# Sheet2.net
KiCad netlist of a schematic drawn in Altium Designer
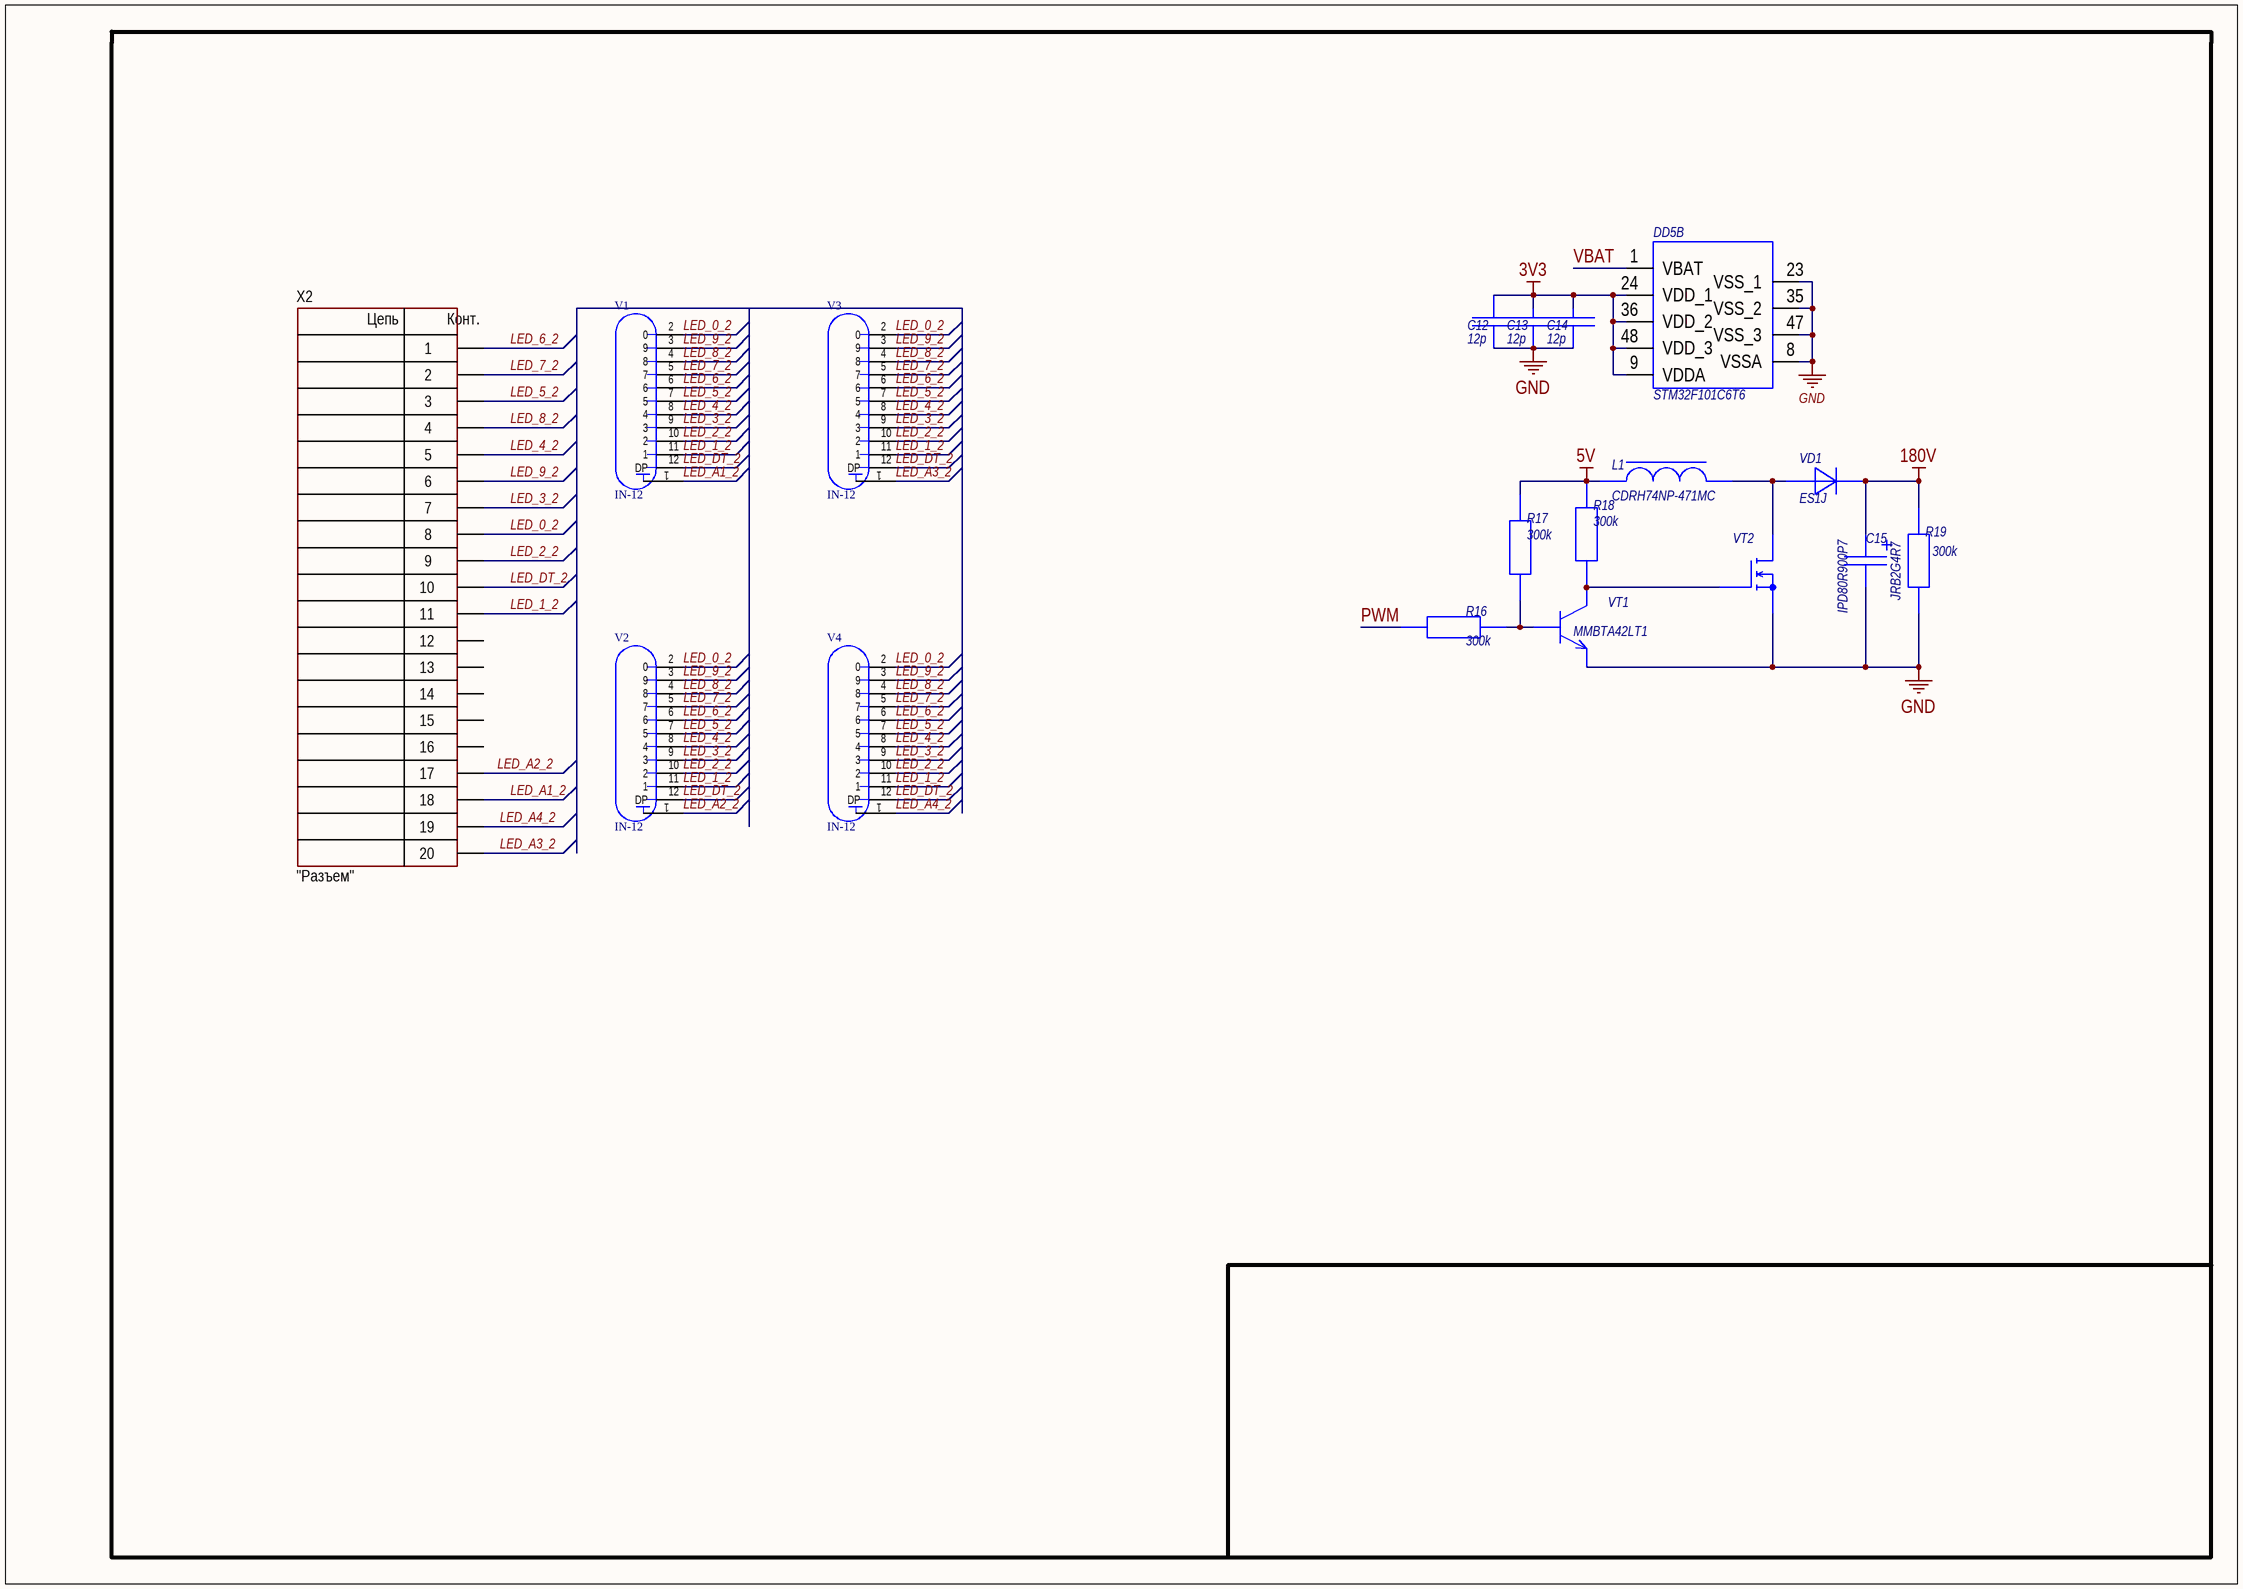
[diagram p0: Sheet2.SchDoc]

(export (version "E")
  (design (tool "Eeschema 10.0.6"))
  (components
    (comp (ref "C12")
      (value "12p")
      (footprint "GRIx4:CAPACITOR 0603")
      (description "Capacitor")
      (libsource (lib "GRIx4_1") (part "SMD-CAP"))
    )
    (comp (ref "C13")
      (value "12p")
      (footprint "GRIx4:CAPACITOR 0603")
      (description "Capacitor")
      (libsource (lib "GRIx4_1") (part "SMD-CAP"))
    )
    (comp (ref "C14")
      (value "12p")
      (footprint "GRIx4:CAPACITOR 0603")
      (description "Capacitor")
      (libsource (lib "GRIx4_1") (part "SMD-CAP"))
    )
    (comp (ref "C15")
      (value "JRB2G4R7")
      (footprint "CAPASITOR R10")
      (description "TC-D")
      (libsource (lib "GRIx4_1") (part "TC-D"))
    )
    (comp (ref "DD5")
      (value "STM32F101C6T6")
      (footprint "48-LQFP")
      (description "Controller")
      (libsource (lib "GRIx4_1") (part "STM32F103C8T6"))
    )
    (comp (ref "L1")
      (value "CDRH74NP-471MC")
      (footprint "SRR0603B")
      (libsource (lib "GRIx4_1") (part "Inductor"))
    )
    (comp (ref "R16")
      (value "300k")
      (footprint "RESISTOR 0603")
      (description "Resistor")
      (libsource (lib "GRIx4_1") (part "SMD-RES_1"))
    )
    (comp (ref "R17")
      (value "300k")
      (footprint "RESISTOR 0603")
      (description "Resistor")
      (libsource (lib "GRIx4_1") (part "SMD-RES_1"))
    )
    (comp (ref "R18")
      (value "300k")
      (footprint "RESISTOR 0603")
      (description "Resistor")
      (libsource (lib "GRIx4_1") (part "SMD-RES_1"))
    )
    (comp (ref "R19")
      (value "300k")
      (footprint "RESISTOR 0805")
      (description "Resistor")
      (libsource (lib "GRIx4_1") (part "SMD-RES_1"))
    )
    (comp (ref "V1")
      (value "IN-12")
      (footprint "GRIx4:DIODE: IN-12")
      (description "Vacuum Indicator")
      (fields (field (name "PUBLISHER") "Altium Limited"))
      (libsource (lib "GRIx4_1") (part "IN-12"))
    )
    (comp (ref "V2")
      (value "IN-12")
      (footprint "GRIx4:DIODE: IN-12")
      (description "Vacuum Indicator")
      (fields (field (name "PUBLISHER") "Altium Limited"))
      (libsource (lib "GRIx4_1") (part "IN-12"))
    )
    (comp (ref "V3")
      (value "IN-12")
      (footprint "GRIx4:DIODE: IN-12")
      (description "Vacuum Indicator")
      (fields (field (name "PUBLISHER") "Altium Limited"))
      (libsource (lib "GRIx4_1") (part "IN-12"))
    )
    (comp (ref "V4")
      (value "IN-12")
      (footprint "GRIx4:DIODE: IN-12")
      (description "Vacuum Indicator")
      (fields (field (name "PUBLISHER") "Altium Limited"))
      (libsource (lib "GRIx4_1") (part "IN-12"))
    )
    (comp (ref "VD1")
      (value "ES1J")
      (footprint "DO-214")
      (description "Diod")
      (libsource (lib "GRIx4_1") (part "D-Diod"))
    )
    (comp (ref "VT1")
      (value "MMBTA42LT1")
      (footprint "GRIx4:SOT-23")
      (description "Transistor")
      (libsource (lib "GRIx4_1") (part "Transistor-NPN"))
    )
    (comp (ref "VT2")
      (value "IPD80R900P7")
      (footprint "DPAK")
      (description "Transistor")
      (libsource (lib "GRIx4_1") (part "Channel-N"))
    )
    (comp (ref "X2")
      (value "~")
      (footprint "GRIx4:CON: PLD-20-rebro")
      (fields
        (field (name "MANUFACTURER") "Connfly")
        (field (name "VALUEMANUFACTURERPARTNUMBER") "Connector, 20pin, 2.54mm, 500VAC, 3A")
        (field (name "PARTNUMBER") "PLD-20")
        (field (name "COMMENTTEXT") "\"Разъем\"")
      )
      (libsource (lib "GRIx4_1") (part "PLD-20-REBRO"))
    )
  )
  (nets
    (net (code "1") (name "/LED_0_2") (class "Default")
      (node (ref "V1") (pin "2") (pinfunction "0_2") (pintype "passive"))
      (node (ref "V2") (pin "2") (pinfunction "0_2") (pintype "passive"))
      (node (ref "V3") (pin "2") (pinfunction "0_2") (pintype "passive"))
      (node (ref "V4") (pin "2") (pinfunction "0_2") (pintype "passive"))
      (node (ref "X2") (pin "8") (pinfunction "8_8") (pintype "power_in"))
    )
    (net (code "2") (name "/LED_1_2") (class "Default")
      (node (ref "V1") (pin "11") (pinfunction "1_11") (pintype "passive"))
      (node (ref "V2") (pin "11") (pinfunction "1_11") (pintype "passive"))
      (node (ref "V3") (pin "11") (pinfunction "1_11") (pintype "passive"))
      (node (ref "V4") (pin "11") (pinfunction "1_11") (pintype "passive"))
      (node (ref "X2") (pin "11") (pinfunction "11_11") (pintype "power_in"))
    )
    (net (code "3") (name "/LED_2_2") (class "Default")
      (node (ref "V1") (pin "10") (pinfunction "2_10") (pintype "passive"))
      (node (ref "V2") (pin "10") (pinfunction "2_10") (pintype "passive"))
      (node (ref "V3") (pin "10") (pinfunction "2_10") (pintype "passive"))
      (node (ref "V4") (pin "10") (pinfunction "2_10") (pintype "passive"))
      (node (ref "X2") (pin "9") (pinfunction "9_9") (pintype "power_in"))
    )
    (net (code "4") (name "/LED_3_2") (class "Default")
      (node (ref "V1") (pin "9") (pinfunction "3_9") (pintype "passive"))
      (node (ref "V2") (pin "9") (pinfunction "3_9") (pintype "passive"))
      (node (ref "V3") (pin "9") (pinfunction "3_9") (pintype "passive"))
      (node (ref "V4") (pin "9") (pinfunction "3_9") (pintype "passive"))
      (node (ref "X2") (pin "7") (pinfunction "7_7") (pintype "power_in"))
    )
    (net (code "5") (name "/LED_4_2") (class "Default")
      (node (ref "V1") (pin "8") (pinfunction "4_8") (pintype "passive"))
      (node (ref "V2") (pin "8") (pinfunction "4_8") (pintype "passive"))
      (node (ref "V3") (pin "8") (pinfunction "4_8") (pintype "passive"))
      (node (ref "V4") (pin "8") (pinfunction "4_8") (pintype "passive"))
      (node (ref "X2") (pin "5") (pinfunction "5_5") (pintype "power_in"))
    )
    (net (code "6") (name "/LED_5_2") (class "Default")
      (node (ref "V1") (pin "7") (pinfunction "5_7") (pintype "passive"))
      (node (ref "V2") (pin "7") (pinfunction "5_7") (pintype "passive"))
      (node (ref "V3") (pin "7") (pinfunction "5_7") (pintype "passive"))
      (node (ref "V4") (pin "7") (pinfunction "5_7") (pintype "passive"))
      (node (ref "X2") (pin "3") (pinfunction "3_3") (pintype "power_in"))
    )
    (net (code "7") (name "/LED_6_2") (class "Default")
      (node (ref "V1") (pin "6") (pinfunction "6_6") (pintype "passive"))
      (node (ref "V2") (pin "6") (pinfunction "6_6") (pintype "passive"))
      (node (ref "V3") (pin "6") (pinfunction "6_6") (pintype "passive"))
      (node (ref "V4") (pin "6") (pinfunction "6_6") (pintype "passive"))
      (node (ref "X2") (pin "1") (pinfunction "1_1") (pintype "passive"))
    )
    (net (code "8") (name "/LED_7_2") (class "Default")
      (node (ref "V1") (pin "5") (pinfunction "7_5") (pintype "passive"))
      (node (ref "V2") (pin "5") (pinfunction "7_5") (pintype "passive"))
      (node (ref "V3") (pin "5") (pinfunction "7_5") (pintype "passive"))
      (node (ref "V4") (pin "5") (pinfunction "7_5") (pintype "passive"))
      (node (ref "X2") (pin "2") (pinfunction "2_2") (pintype "passive"))
    )
    (net (code "9") (name "/LED_8_2") (class "Default")
      (node (ref "V1") (pin "4") (pinfunction "8_4") (pintype "passive"))
      (node (ref "V2") (pin "4") (pinfunction "8_4") (pintype "passive"))
      (node (ref "V3") (pin "4") (pinfunction "8_4") (pintype "passive"))
      (node (ref "V4") (pin "4") (pinfunction "8_4") (pintype "passive"))
      (node (ref "X2") (pin "4") (pinfunction "4_4") (pintype "power_in"))
    )
    (net (code "10") (name "/LED_9_2") (class "Default")
      (node (ref "V1") (pin "3") (pinfunction "9_3") (pintype "passive"))
      (node (ref "V2") (pin "3") (pinfunction "9_3") (pintype "passive"))
      (node (ref "V3") (pin "3") (pinfunction "9_3") (pintype "passive"))
      (node (ref "V4") (pin "3") (pinfunction "9_3") (pintype "passive"))
      (node (ref "X2") (pin "6") (pinfunction "6_6") (pintype "power_in"))
    )
    (net (code "11") (name "/LED_A1_2") (class "Default")
      (node (ref "V1") (pin "1") (pinfunction "A_1") (pintype "passive"))
      (node (ref "X2") (pin "18") (pinfunction "18_18") (pintype "power_in"))
    )
    (net (code "12") (name "/LED_A2_2") (class "Default")
      (node (ref "V2") (pin "1") (pinfunction "A_1") (pintype "passive"))
      (node (ref "X2") (pin "17") (pinfunction "17_17") (pintype "power_in"))
    )
    (net (code "13") (name "/LED_A3_2") (class "Default")
      (node (ref "V3") (pin "1") (pinfunction "A_1") (pintype "passive"))
      (node (ref "X2") (pin "20") (pinfunction "20_20") (pintype "power_in"))
    )
    (net (code "14") (name "/LED_A4_2") (class "Default")
      (node (ref "V4") (pin "1") (pinfunction "A_1") (pintype "passive"))
      (node (ref "X2") (pin "19") (pinfunction "19_19") (pintype "power_in"))
    )
    (net (code "15") (name "/LED_DT_2") (class "Default")
      (node (ref "V1") (pin "12") (pinfunction "DP_12") (pintype "passive"))
      (node (ref "V2") (pin "12") (pinfunction "DP_12") (pintype "passive"))
      (node (ref "V3") (pin "12") (pinfunction "DP_12") (pintype "passive"))
      (node (ref "V4") (pin "12") (pinfunction "DP_12") (pintype "passive"))
      (node (ref "X2") (pin "10") (pinfunction "10_10") (pintype "power_in"))
    )
    (net (code "16") (name "/PWM") (class "Default")
      (node (ref "R16") (pin "2") (pinfunction "2_2") (pintype "passive"))
    )
    (net (code "17") (name "/VBAT") (class "Default")
      (node (ref "DD5") (pin "1") (pinfunction "VBAT_1") (pintype "power_in"))
    )
    (net (code "18") (name "3V3") (class "Default")
      (node (ref "C12") (pin "2") (pinfunction "2_2") (pintype "passive"))
      (node (ref "C13") (pin "2") (pinfunction "2_2") (pintype "passive"))
      (node (ref "C14") (pin "2") (pinfunction "2_2") (pintype "passive"))
      (node (ref "DD5") (pin "24") (pinfunction "VDD_1_24") (pintype "power_in"))
      (node (ref "DD5") (pin "36") (pinfunction "VDD_2_36") (pintype "power_in"))
      (node (ref "DD5") (pin "48") (pinfunction "VDD_3_48") (pintype "power_in"))
      (node (ref "DD5") (pin "9") (pinfunction "VDDA_9") (pintype "power_in"))
    )
    (net (code "19") (name "5V") (class "Default")
      (node (ref "L1") (pin "1") (pinfunction "1_1") (pintype "passive"))
      (node (ref "R17") (pin "1") (pinfunction "1_1") (pintype "passive"))
      (node (ref "R18") (pin "1") (pinfunction "1_1") (pintype "passive"))
    )
    (net (code "20") (name "180V") (class "Default")
      (node (ref "C15") (pin "1") (pinfunction "1_1") (pintype "passive"))
      (node (ref "R19") (pin "1") (pinfunction "1_1") (pintype "passive"))
      (node (ref "VD1") (pin "1") (pinfunction "А_1") (pintype "passive"))
    )
    (net (code "21") (name "GND") (class "Default")
      (node (ref "C12") (pin "1") (pinfunction "1_1") (pintype "passive"))
      (node (ref "C13") (pin "1") (pinfunction "1_1") (pintype "passive"))
      (node (ref "C14") (pin "1") (pinfunction "1_1") (pintype "passive"))
      (node (ref "C15") (pin "2") (pinfunction "2_2") (pintype "passive"))
      (node (ref "DD5") (pin "23") (pinfunction "VSS_1_23") (pintype "power_in"))
      (node (ref "DD5") (pin "35") (pinfunction "VSS_2_35") (pintype "power_in"))
      (node (ref "DD5") (pin "47") (pinfunction "VSS_3_47") (pintype "power_in"))
      (node (ref "DD5") (pin "8") (pinfunction "VSSA_8") (pintype "power_in"))
      (node (ref "R19") (pin "2") (pinfunction "2_2") (pintype "passive"))
      (node (ref "VT1") (pin "3") (pinfunction "Э_3") (pintype "passive"))
      (node (ref "VT2") (pin "3") (pinfunction "S_3") (pintype "passive"))
    )
    (net (code "22") (name "Net-(VD1-К)") (class "Default")
      (node (ref "L1") (pin "2") (pinfunction "2_2") (pintype "passive"))
      (node (ref "VD1") (pin "2") (pinfunction "К_2") (pintype "passive"))
      (node (ref "VT2") (pin "2") (pinfunction "D_2") (pintype "passive"))
    )
    (net (code "23") (name "Net-(VT1-Б)") (class "Default")
      (node (ref "R16") (pin "1") (pinfunction "1_1") (pintype "passive"))
      (node (ref "R17") (pin "2") (pinfunction "2_2") (pintype "passive"))
      (node (ref "VT1") (pin "1") (pinfunction "Б_1") (pintype "passive"))
    )
    (net (code "24") (name "Net-(VT1-К)") (class "Default")
      (node (ref "R18") (pin "2") (pinfunction "2_2") (pintype "passive"))
      (node (ref "VT1") (pin "2") (pinfunction "К_2") (pintype "passive"))
      (node (ref "VT2") (pin "1") (pinfunction "G_1") (pintype "passive"))
    )
    (net (code "25") (name "unconnected-(X2-Pad12)") (class "Default")
      (node (ref "X2") (pin "12") (pinfunction "12_12") (pintype "power_in"))
    )
    (net (code "26") (name "unconnected-(X2-Pad13)") (class "Default")
      (node (ref "X2") (pin "13") (pinfunction "13_13") (pintype "power_in"))
    )
    (net (code "27") (name "unconnected-(X2-Pad14)") (class "Default")
      (node (ref "X2") (pin "14") (pinfunction "14_14") (pintype "power_in"))
    )
    (net (code "28") (name "unconnected-(X2-Pad15)") (class "Default")
      (node (ref "X2") (pin "15") (pinfunction "15_15") (pintype "power_in"))
    )
    (net (code "29") (name "unconnected-(X2-Pad16)") (class "Default")
      (node (ref "X2") (pin "16") (pinfunction "16_16") (pintype "power_in"))
    )
  )
)
